# LTC6820.net
KiCad netlist of a schematic drawn in Altium Designer
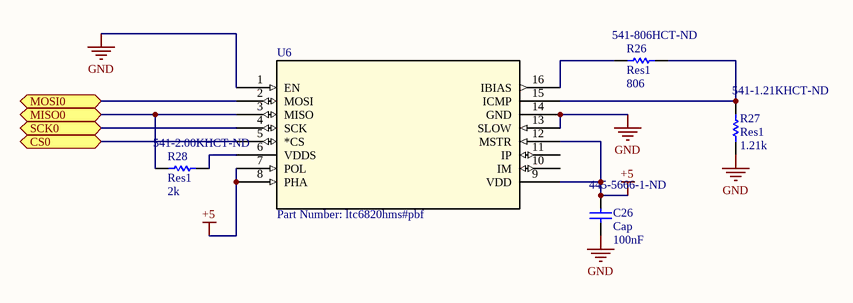
[diagram p0: LTC6820.SchDoc]

(export (version "E")
  (design (tool "Eeschema 10.0.6"))
  (components
    (comp (ref "C26")
      (value "Cap")
      (footprint "J1-0603")
      (description "TDK - CGA3E2X7R1H104K080AA. - CERAMIC CAPACITOR, 0.1UF, 50V, X7R, 0603, FULL REEL")
      (fields
        (field (name "ALTIUM_VALUE") "100nF")
        (field (name "SUPPLIER PART NUMBER 1") "445-5666-1-ND")
        (field (name "MANUFACTURER") "TDK")
        (field (name "MANUFACTURER PART NUMBER") "CGA3E2X7R1H104K080AA")
        (field (name "PUBLISHER") "Altium Limited")
      )
      (libsource (lib "Miscellaneous Devices") (part "Cap"))
    )
    (comp (ref "R26")
      (value "Res1")
      (footprint "J1-0603")
      (description "RES SMD 806 OHM 1% 1/10W 0603")
      (fields
        (field (name "ALTIUM_VALUE") "806")
        (field (name "SUPPLIER PART NUMBER 1") "541-806HCT-ND")
        (field (name "MANUFACTURER") "Vishay")
        (field (name "MANUFACTURER PART NUMBER") "CRCW0603806RFKEA")
        (field (name "PUBLISHER") "Altium Limited")
      )
      (libsource (lib "Miscellaneous Devices") (part "Res1"))
    )
    (comp (ref "R27")
      (value "Res1")
      (footprint "J1-0603")
      (description "Res Thick Film 0603 1.21K Ohm 1% 1/10W 100ppm/C Molded SMD Paper T/R")
      (fields
        (field (name "ALTIUM_VALUE") "1.21k")
        (field (name "SUPPLIER PART NUMBER 1") "541-1.21KHCT-ND")
        (field (name "MANUFACTURER") "Vishay")
        (field (name "MANUFACTURER PART NUMBER") "CRCW06031K21FKEA")
        (field (name "PUBLISHER") "Altium Limited")
      )
      (libsource (lib "Miscellaneous Devices") (part "Res1"))
    )
    (comp (ref "R28")
      (value "Res1")
      (footprint "J1-0603")
      (description "D11/CRCW0603 100 2K 1% ET1 e3")
      (fields
        (field (name "ALTIUM_VALUE") "2k")
        (field (name "SUPPLIER PART NUMBER 1") "541-2.00KHCT-ND")
        (field (name "MANUFACTURER") "Vishay")
        (field (name "MANUFACTURER PART NUMBER") "CRCW06032K00FKEA")
        (field (name "PUBLISHER") "Altium Limited")
      )
      (libsource (lib "Miscellaneous Devices") (part "Res1"))
    )
    (comp (ref "U6")
      (value "Part Number: ltc6820hms#pbf")
      (footprint "MSOP-16_MS")
      (description "No Description Available")
      (fields
        (field (name "MANUFACTURER_PART_NUMBER") "ltc6820hms#pbf")
        (field (name "COPYRIGHT") "Copyright (C) 2018 Accelerated Designs. All rights reserved")
      )
      (libsource (lib "LTC6820") (part "LTC6820HMSPBF"))
    )
  )
  (nets
    (net (code "1") (name "+5") (class "Default")
      (node (ref "C26") (pin "2") (pinfunction "2_2") (pintype "passive"))
      (node (ref "U6") (pin "12") (pinfunction "MSTR_12") (pintype "input"))
      (node (ref "U6") (pin "7") (pinfunction "POL_7") (pintype "input"))
      (node (ref "U6") (pin "8") (pinfunction "PHA_8") (pintype "input"))
      (node (ref "U6") (pin "9") (pinfunction "VDD_9") (pintype "power_in"))
    )
    (net (code "2") (name "/CS0") (class "Default")
      (node (ref "U6") (pin "5") (pinfunction "*CS_5") (pintype "bidirectional"))
    )
    (net (code "3") (name "/MISO0") (class "Default")
      (node (ref "R28") (pin "1") (pinfunction "1_1") (pintype "passive"))
      (node (ref "U6") (pin "3") (pinfunction "MISO_3") (pintype "bidirectional"))
    )
    (net (code "4") (name "/MOSI0") (class "Default")
      (node (ref "U6") (pin "2") (pinfunction "MOSI_2") (pintype "bidirectional"))
    )
    (net (code "5") (name "/SCK0") (class "Default")
      (node (ref "U6") (pin "4") (pinfunction "SCK_4") (pintype "bidirectional"))
    )
    (net (code "6") (name "GND") (class "Default")
      (node (ref "C26") (pin "1") (pinfunction "1_1") (pintype "passive"))
      (node (ref "R27") (pin "1") (pinfunction "1_1") (pintype "passive"))
      (node (ref "U6") (pin "1") (pinfunction "EN_1") (pintype "input"))
      (node (ref "U6") (pin "13") (pinfunction "SLOW_13") (pintype "input"))
      (node (ref "U6") (pin "14") (pinfunction "GND_14") (pintype "power_in"))
    )
    (net (code "7") (name "Net-(U6-IBIAS)") (class "Default")
      (node (ref "R26") (pin "1") (pinfunction "1_1") (pintype "passive"))
      (node (ref "U6") (pin "16") (pinfunction "IBIAS_16") (pintype "output"))
    )
    (net (code "8") (name "Net-(U6-ICMP)") (class "Default")
      (node (ref "R26") (pin "2") (pinfunction "2_2") (pintype "passive"))
      (node (ref "R27") (pin "2") (pinfunction "2_2") (pintype "passive"))
      (node (ref "U6") (pin "15") (pinfunction "ICMP_15") (pintype "passive"))
    )
    (net (code "9") (name "Net-(U6-VDDS)") (class "Default")
      (node (ref "R28") (pin "2") (pinfunction "2_2") (pintype "passive"))
      (node (ref "U6") (pin "6") (pinfunction "VDDS_6") (pintype "power_in"))
    )
    (net (code "10") (name "unconnected-(U6-IM-Pad10)") (class "Default")
      (node (ref "U6") (pin "10") (pinfunction "IM_10") (pintype "bidirectional"))
    )
    (net (code "11") (name "unconnected-(U6-IP-Pad11)") (class "Default")
      (node (ref "U6") (pin "11") (pinfunction "IP_11") (pintype "bidirectional"))
    )
  )
)
